# esp32c3.net
KiCad netlist of a schematic drawn in EasyEDA
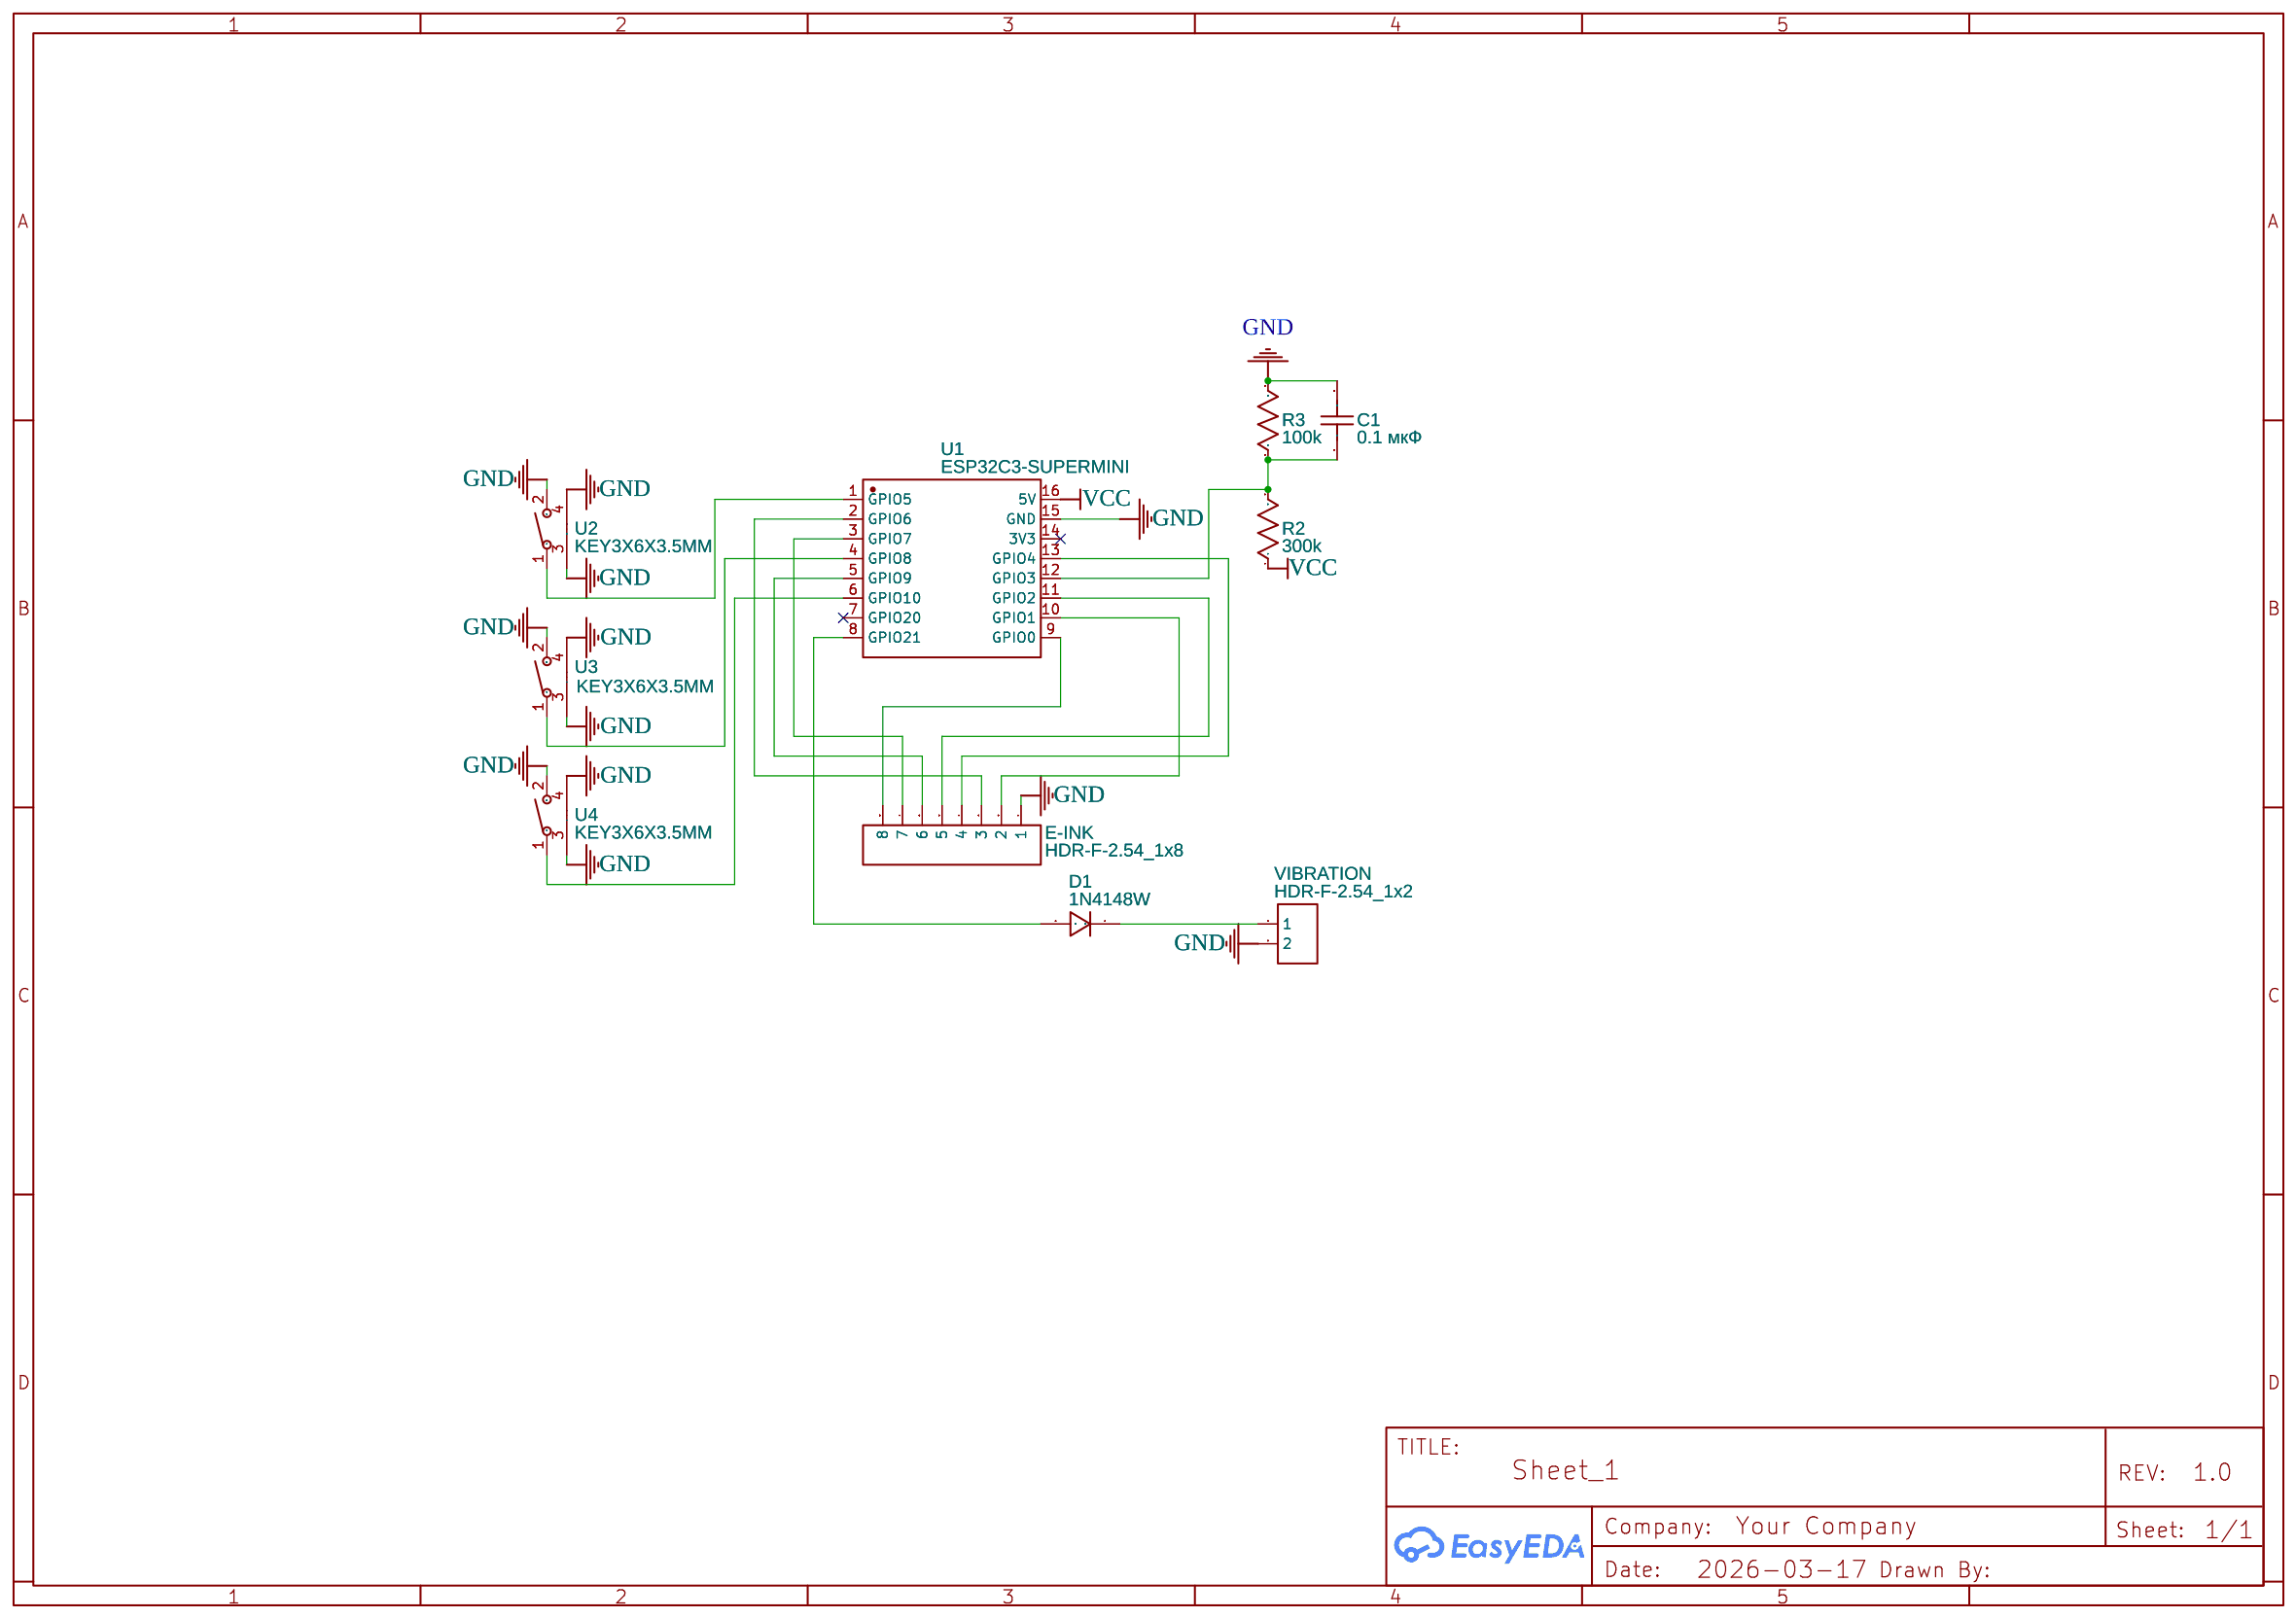
[diagram p0: schematic sheet]

(export (version "E")
  (design (tool "Eeschema 10.0.6"))
  (components
    (comp (ref "C1") (value "0.1 мкФ") (libsource (lib "") (part "C_0603_US")))
    (comp (ref "D1")
      (value "1N4148W")
      (fields (field (name "Manufacturer") "Tak Cheong"))
      (libsource (lib "") (part "1N4148W"))
    )
    (comp (ref "E-INK") (value "HDR-F-2.54_1x8") (libsource (lib "") (part "HDR-F-2.54_1x8")))
    (comp (ref "R2") (value "300k") (libsource (lib "") (part "R_0805_US")))
    (comp (ref "R3") (value "100k") (libsource (lib "") (part "R_0603_US")))
    (comp (ref "U1")
      (value "ESP32C3-SUPERMINI")
      (fields (field (name "Manufacturer Part") "ESP32C3-SuperMini"))
      (libsource (lib "") (part "ESP32C3-SUPERMINI"))
    )
    (comp (ref "U2") (value "KEY3X6X3.5MM") (libsource (lib "") (part "KEY3X6X3.5MM")))
    (comp (ref "U3") (value "KEY3X6X3.5MM") (libsource (lib "") (part "KEY3X6X3.5MM")))
    (comp (ref "U4") (value "KEY3X6X3.5MM") (libsource (lib "") (part "KEY3X6X3.5MM")))
    (comp (ref "VIBRATION") (value "HDR-F-2.54_1x2") (libsource (lib "") (part "HDR-F-2.54_1x2")))
  )
  (nets
    (net (code "1") (name "GND") (class "Default")
      (node (ref "C1") (pin "2") (pinfunction "2_2") (pintype "unspecified"))
      (node (ref "E-INK") (pin "1") (pinfunction "1_1") (pintype "unspecified"))
      (node (ref "R3") (pin "2") (pinfunction "2_2") (pintype "unspecified"))
      (node (ref "U1") (pin "15") (pinfunction "GND_15") (pintype "unspecified"))
      (node (ref "U2") (pin "2") (pinfunction "2_2") (pintype "unspecified"))
      (node (ref "U2") (pin "3") (pinfunction "3_3") (pintype "unspecified"))
      (node (ref "U2") (pin "4") (pinfunction "4_4") (pintype "unspecified"))
      (node (ref "U3") (pin "2") (pinfunction "2_2") (pintype "unspecified"))
      (node (ref "U3") (pin "3") (pinfunction "3_3") (pintype "unspecified"))
      (node (ref "U3") (pin "4") (pinfunction "4_4") (pintype "unspecified"))
      (node (ref "U4") (pin "2") (pinfunction "2_2") (pintype "unspecified"))
      (node (ref "U4") (pin "3") (pinfunction "3_3") (pintype "unspecified"))
      (node (ref "U4") (pin "4") (pinfunction "4_4") (pintype "unspecified"))
      (node (ref "VIBRATION") (pin "2") (pinfunction "2_2") (pintype "input"))
    )
    (net (code "2") (name "Net-(D1-Pad1)") (class "Default")
      (node (ref "D1") (pin "1") (pinfunction "1_1") (pintype "unspecified"))
      (node (ref "VIBRATION") (pin "1") (pinfunction "1_1") (pintype "input"))
    )
    (net (code "3") (name "Net-(U1-GPIO0)") (class "Default")
      (node (ref "E-INK") (pin "8") (pinfunction "8_8") (pintype "unspecified"))
      (node (ref "U1") (pin "9") (pinfunction "GPIO0_9") (pintype "unspecified"))
    )
    (net (code "4") (name "Net-(U1-GPIO1)") (class "Default")
      (node (ref "E-INK") (pin "2") (pinfunction "2_2") (pintype "unspecified"))
      (node (ref "U1") (pin "10") (pinfunction "GPIO1_10") (pintype "unspecified"))
    )
    (net (code "5") (name "Net-(U1-GPIO2)") (class "Default")
      (node (ref "E-INK") (pin "5") (pinfunction "5_5") (pintype "unspecified"))
      (node (ref "U1") (pin "11") (pinfunction "GPIO2_11") (pintype "unspecified"))
    )
    (net (code "6") (name "Net-(U1-GPIO3)") (class "Default")
      (node (ref "C1") (pin "1") (pinfunction "1_1") (pintype "unspecified"))
      (node (ref "R2") (pin "2") (pinfunction "2_2") (pintype "unspecified"))
      (node (ref "R3") (pin "1") (pinfunction "1_1") (pintype "unspecified"))
      (node (ref "U1") (pin "12") (pinfunction "GPIO3_12") (pintype "unspecified"))
    )
    (net (code "7") (name "Net-(U1-GPIO4)") (class "Default")
      (node (ref "E-INK") (pin "4") (pinfunction "4_4") (pintype "unspecified"))
      (node (ref "U1") (pin "13") (pinfunction "GPIO4_13") (pintype "unspecified"))
    )
    (net (code "8") (name "Net-(U1-GPIO5)") (class "Default")
      (node (ref "U1") (pin "1") (pinfunction "GPIO5_1") (pintype "unspecified"))
      (node (ref "U2") (pin "1") (pinfunction "1_1") (pintype "unspecified"))
    )
    (net (code "9") (name "Net-(U1-GPIO6)") (class "Default")
      (node (ref "E-INK") (pin "3") (pinfunction "3_3") (pintype "unspecified"))
      (node (ref "U1") (pin "2") (pinfunction "GPIO6_2") (pintype "unspecified"))
    )
    (net (code "10") (name "Net-(U1-GPIO7)") (class "Default")
      (node (ref "E-INK") (pin "7") (pinfunction "7_7") (pintype "unspecified"))
      (node (ref "U1") (pin "3") (pinfunction "GPIO7_3") (pintype "unspecified"))
    )
    (net (code "11") (name "Net-(U1-GPIO8)") (class "Default")
      (node (ref "U1") (pin "4") (pinfunction "GPIO8_4") (pintype "unspecified"))
      (node (ref "U3") (pin "1") (pinfunction "1_1") (pintype "unspecified"))
    )
    (net (code "12") (name "Net-(U1-GPIO9)") (class "Default")
      (node (ref "E-INK") (pin "6") (pinfunction "6_6") (pintype "unspecified"))
      (node (ref "U1") (pin "5") (pinfunction "GPIO9_5") (pintype "unspecified"))
    )
    (net (code "13") (name "Net-(U1-GPIO10)") (class "Default")
      (node (ref "U1") (pin "6") (pinfunction "GPIO10_6") (pintype "unspecified"))
      (node (ref "U4") (pin "1") (pinfunction "1_1") (pintype "unspecified"))
    )
    (net (code "14") (name "Net-(U1-GPIO21)") (class "Default")
      (node (ref "D1") (pin "2") (pinfunction "2_2") (pintype "unspecified"))
      (node (ref "U1") (pin "8") (pinfunction "GPIO21_8") (pintype "unspecified"))
    )
    (net (code "15") (name "VCC") (class "Default")
      (node (ref "R2") (pin "1") (pinfunction "1_1") (pintype "unspecified"))
      (node (ref "U1") (pin "16") (pinfunction "5V_16") (pintype "unspecified"))
    )
    (net (code "16") (name "unconnected-(U1-3V3-Pad14)") (class "Default")
      (node (ref "U1") (pin "14") (pinfunction "3V3_14") (pintype "unspecified+no_connect"))
    )
    (net (code "17") (name "unconnected-(U1-GPIO20-Pad7)") (class "Default")
      (node (ref "U1") (pin "7") (pinfunction "GPIO20_7") (pintype "unspecified+no_connect"))
    )
  )
)
